# NU-SYNTHS_MIDICV_CONN.net
KiCad netlist of a schematic drawn in Altium Designer
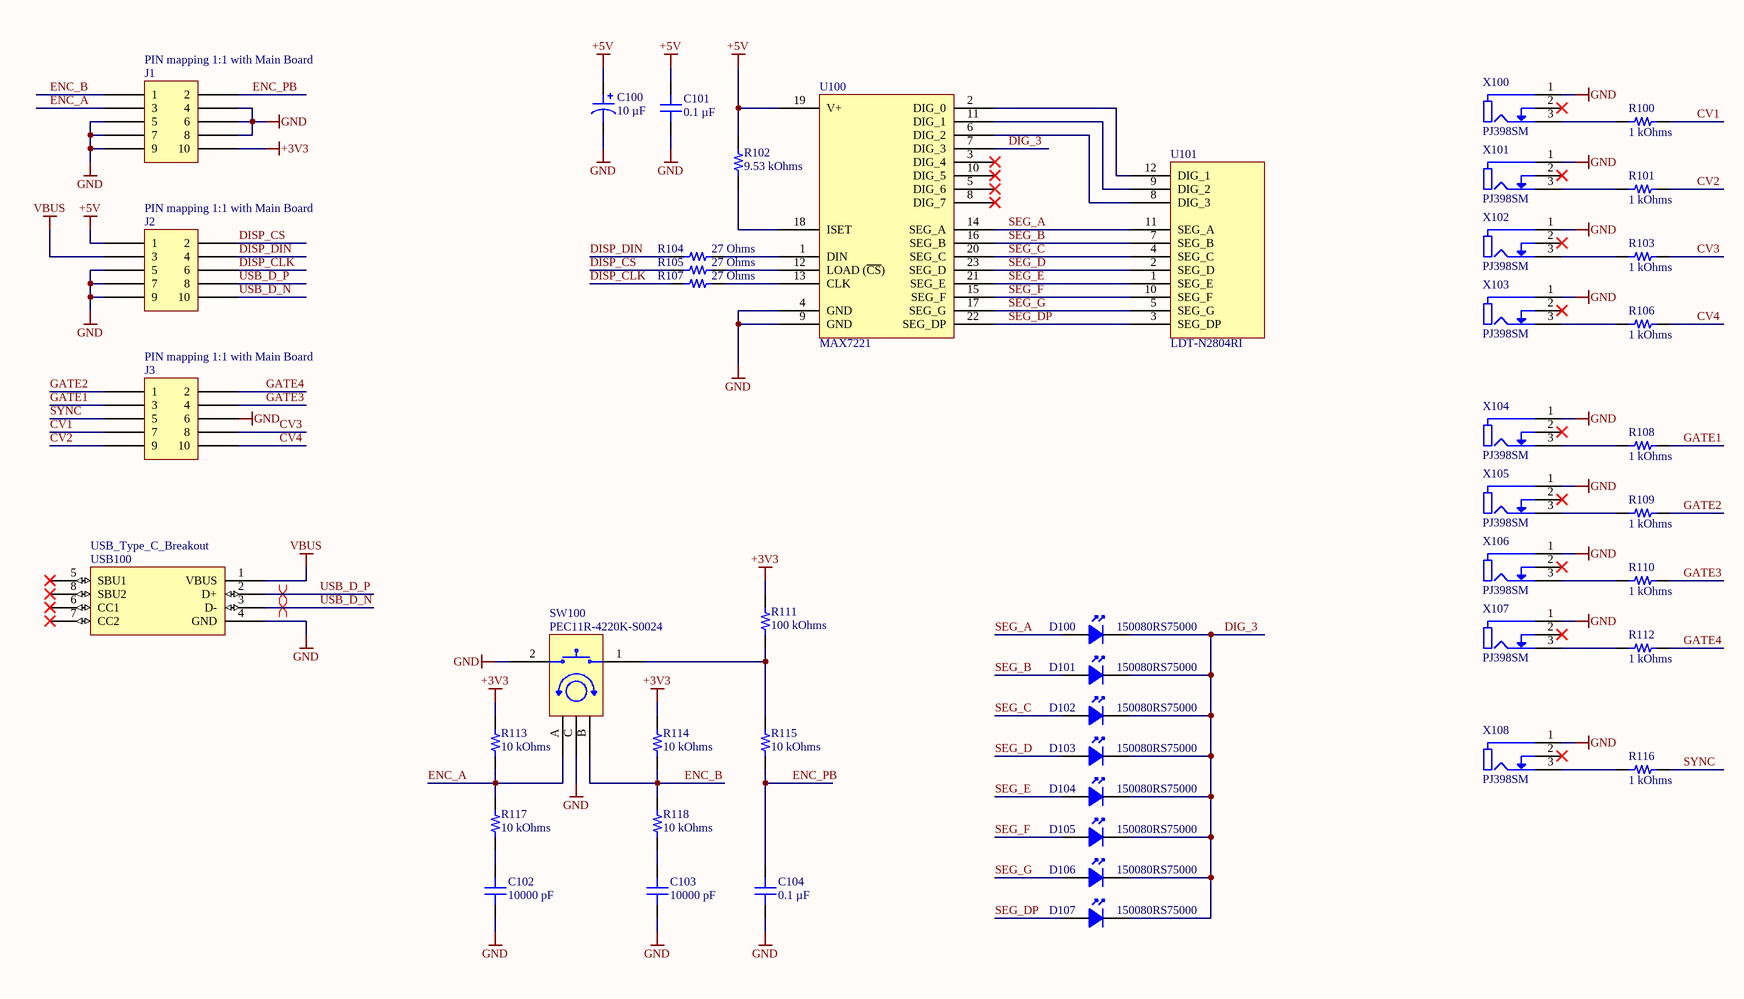
[diagram p0: NU-SYNTHS_MIDICV_CONN.SchDoc]

(export (version "E")
  (design (tool "Eeschema 10.0.6"))
  (components
    (comp (ref "C100")
      (value "10 µF")
      (footprint "CAP ALSMD 4.3MM H5.4MM")
      (description "CAP ALUM 10UF 20% 16V SMD")
      (fields (field (name "PART NUMBER") "UWX1C100MCL1GB") (field (name "MANUFACTURER") "Nichicon"))
      (libsource (lib "Celestial Altium Library") (part "Polarised Capacitor"))
    )
    (comp (ref "C101")
      (value "0.1 µF")
      (footprint "CAP 0603_1608")
      (description "CAP CER 0.1UF 25V Y5V 0603")
      (fields (field (name "PART NUMBER") "CC0603MRY5V8BB104") (field (name "MANUFACTURER") "Yageo"))
      (libsource (lib "Celestial Altium Library") (part "Capacitor"))
    )
    (comp (ref "C102")
      (value "10000 pF")
      (footprint "CAP 0603_1608")
      (description "CAP CER 10000PF 50V X7R 0603")
      (fields (field (name "PART NUMBER") "CC0603KRX7R9BB103") (field (name "MANUFACTURER") "Yageo"))
      (libsource (lib "Celestial Altium Library") (part "Capacitor"))
    )
    (comp (ref "C103")
      (value "10000 pF")
      (footprint "CAP 0603_1608")
      (description "CAP CER 10000PF 50V X7R 0603")
      (fields (field (name "PART NUMBER") "CC0603KRX7R9BB103") (field (name "MANUFACTURER") "Yageo"))
      (libsource (lib "Celestial Altium Library") (part "Capacitor"))
    )
    (comp (ref "C104")
      (value "0.1 µF")
      (footprint "CAP 0603_1608")
      (description "CAP CER 0.1UF 25V Y5V 0603")
      (fields (field (name "PART NUMBER") "CC0603MRY5V8BB104") (field (name "MANUFACTURER") "Yageo"))
      (libsource (lib "Celestial Altium Library") (part "Capacitor"))
    )
    (comp (ref "D100")
      (value "150080RS75000")
      (footprint "LED0805_PIPE")
      (description "Standard LEDs - SMD WL-SMCW SMDMono TpVw Waterclr 0805 Red")
      (libsource (lib "LabratsSynthLib") (part "150080RS75000"))
    )
    (comp (ref "D101")
      (value "150080RS75000")
      (footprint "LED0805_PIPE")
      (description "Standard LEDs - SMD WL-SMCW SMDMono TpVw Waterclr 0805 Red")
      (libsource (lib "LabratsSynthLib") (part "150080RS75000"))
    )
    (comp (ref "D102")
      (value "150080RS75000")
      (footprint "LED0805_PIPE")
      (description "Standard LEDs - SMD WL-SMCW SMDMono TpVw Waterclr 0805 Red")
      (libsource (lib "LabratsSynthLib") (part "150080RS75000"))
    )
    (comp (ref "D103")
      (value "150080RS75000")
      (footprint "LED0805_PIPE")
      (description "Standard LEDs - SMD WL-SMCW SMDMono TpVw Waterclr 0805 Red")
      (libsource (lib "LabratsSynthLib") (part "150080RS75000"))
    )
    (comp (ref "D104")
      (value "150080RS75000")
      (footprint "LED0805_PIPE")
      (description "Standard LEDs - SMD WL-SMCW SMDMono TpVw Waterclr 0805 Red")
      (libsource (lib "LabratsSynthLib") (part "150080RS75000"))
    )
    (comp (ref "D105")
      (value "150080RS75000")
      (footprint "LED0805_PIPE")
      (description "Standard LEDs - SMD WL-SMCW SMDMono TpVw Waterclr 0805 Red")
      (libsource (lib "LabratsSynthLib") (part "150080RS75000"))
    )
    (comp (ref "D106")
      (value "150080RS75000")
      (footprint "LED0805_PIPE")
      (description "Standard LEDs - SMD WL-SMCW SMDMono TpVw Waterclr 0805 Red")
      (libsource (lib "LabratsSynthLib") (part "150080RS75000"))
    )
    (comp (ref "D107")
      (value "150080RS75000")
      (footprint "LED0805_PIPE")
      (description "Standard LEDs - SMD WL-SMCW SMDMono TpVw Waterclr 0805 Red")
      (libsource (lib "LabratsSynthLib") (part "150080RS75000"))
    )
    (comp (ref "J1")
      (value "GENERIC_HEADER_2x5")
      (footprint "HEADER_2x5_TH_MALE_MIRRORED")
      (description "Generic 2x5 header")
      (libsource (lib "LabratsSynthLib") (part "GENERIC_HEADER_2x5"))
    )
    (comp (ref "J2")
      (value "GENERIC_HEADER_2x5")
      (footprint "HEADER_2x5_TH_MALE_MIRRORED")
      (description "Generic 2x5 header")
      (libsource (lib "LabratsSynthLib") (part "GENERIC_HEADER_2x5"))
    )
    (comp (ref "J3")
      (value "GENERIC_HEADER_2x5")
      (footprint "HEADER_2x5_TH_MALE_MIRRORED")
      (description "Generic 2x5 header")
      (libsource (lib "LabratsSynthLib") (part "GENERIC_HEADER_2x5"))
    )
    (comp (ref "R100")
      (value "1 kOhms")
      (footprint "RES 0603_1608")
      (description "RES 1K OHM 1% 1/10W 0603")
      (fields (field (name "PART NUMBER") "CRCW06031K00FKEAC") (field (name "MANUFACTURER") "Vishay Dale"))
      (libsource (lib "Celestial Altium Library") (part "Resistor"))
    )
    (comp (ref "R101")
      (value "1 kOhms")
      (footprint "RES 0603_1608")
      (description "RES 1K OHM 1% 1/10W 0603")
      (fields (field (name "PART NUMBER") "CRCW06031K00FKEAC") (field (name "MANUFACTURER") "Vishay Dale"))
      (libsource (lib "Celestial Altium Library") (part "Resistor"))
    )
    (comp (ref "R102")
      (value "9.53 kOhms")
      (footprint "RES 0603_1608")
      (description "RES SMD 9.53K OHM 1% 1/10W 0603")
      (fields (field (name "PART NUMBER") "CRCW06039K53FKEA") (field (name "MANUFACTURER") "Vishay Dale"))
      (libsource (lib "Celestial Altium Library") (part "Resistor"))
    )
    (comp (ref "R103")
      (value "1 kOhms")
      (footprint "RES 0603_1608")
      (description "RES 1K OHM 1% 1/10W 0603")
      (fields (field (name "PART NUMBER") "CRCW06031K00FKEAC") (field (name "MANUFACTURER") "Vishay Dale"))
      (libsource (lib "Celestial Altium Library") (part "Resistor"))
    )
    (comp (ref "R104")
      (value "27 Ohms")
      (footprint "RES 0603_1608")
      (description "RES SMD 27 OHM 1% 1/10W 0603")
      (fields (field (name "PART NUMBER") "CRCW060327R0FKEA") (field (name "MANUFACTURER") "Vishay Dale"))
      (libsource (lib "Celestial Altium Library") (part "Resistor"))
    )
    (comp (ref "R105")
      (value "27 Ohms")
      (footprint "RES 0603_1608")
      (description "RES SMD 27 OHM 1% 1/10W 0603")
      (fields (field (name "PART NUMBER") "CRCW060327R0FKEA") (field (name "MANUFACTURER") "Vishay Dale"))
      (libsource (lib "Celestial Altium Library") (part "Resistor"))
    )
    (comp (ref "R106")
      (value "1 kOhms")
      (footprint "RES 0603_1608")
      (description "RES 1K OHM 1% 1/10W 0603")
      (fields (field (name "PART NUMBER") "CRCW06031K00FKEAC") (field (name "MANUFACTURER") "Vishay Dale"))
      (libsource (lib "Celestial Altium Library") (part "Resistor"))
    )
    (comp (ref "R107")
      (value "27 Ohms")
      (footprint "RES 0603_1608")
      (description "RES SMD 27 OHM 1% 1/10W 0603")
      (fields (field (name "PART NUMBER") "CRCW060327R0FKEA") (field (name "MANUFACTURER") "Vishay Dale"))
      (libsource (lib "Celestial Altium Library") (part "Resistor"))
    )
    (comp (ref "R108")
      (value "1 kOhms")
      (footprint "RES 0603_1608")
      (description "RES 1K OHM 1% 1/10W 0603")
      (fields (field (name "PART NUMBER") "CRCW06031K00FKEAC") (field (name "MANUFACTURER") "Vishay Dale"))
      (libsource (lib "Celestial Altium Library") (part "Resistor"))
    )
    (comp (ref "R109")
      (value "1 kOhms")
      (footprint "RES 0603_1608")
      (description "RES 1K OHM 1% 1/10W 0603")
      (fields (field (name "PART NUMBER") "CRCW06031K00FKEAC") (field (name "MANUFACTURER") "Vishay Dale"))
      (libsource (lib "Celestial Altium Library") (part "Resistor"))
    )
    (comp (ref "R110")
      (value "1 kOhms")
      (footprint "RES 0603_1608")
      (description "RES 1K OHM 1% 1/10W 0603")
      (fields (field (name "PART NUMBER") "CRCW06031K00FKEAC") (field (name "MANUFACTURER") "Vishay Dale"))
      (libsource (lib "Celestial Altium Library") (part "Resistor"))
    )
    (comp (ref "R111")
      (value "100 kOhms")
      (footprint "RES 0603_1608")
      (description "RES 100K OHM 1% 1/10W 0603")
      (fields (field (name "PART NUMBER") "CRCW0603100KFKEAC") (field (name "MANUFACTURER") "Vishay Dale"))
      (libsource (lib "Celestial Altium Library") (part "Resistor"))
    )
    (comp (ref "R112")
      (value "1 kOhms")
      (footprint "RES 0603_1608")
      (description "RES 1K OHM 1% 1/10W 0603")
      (fields (field (name "PART NUMBER") "CRCW06031K00FKEAC") (field (name "MANUFACTURER") "Vishay Dale"))
      (libsource (lib "Celestial Altium Library") (part "Resistor"))
    )
    (comp (ref "R113")
      (value "10 kOhms")
      (footprint "RES 0603_1608")
      (description "RES SMD 10K OHM 1% 1/10W 0603")
      (fields (field (name "PART NUMBER") "CRCW060310K0FKTA") (field (name "MANUFACTURER") "Vishay Dale"))
      (libsource (lib "Celestial Altium Library") (part "Resistor"))
    )
    (comp (ref "R114")
      (value "10 kOhms")
      (footprint "RES 0603_1608")
      (description "RES SMD 10K OHM 1% 1/10W 0603")
      (fields (field (name "PART NUMBER") "CRCW060310K0FKTA") (field (name "MANUFACTURER") "Vishay Dale"))
      (libsource (lib "Celestial Altium Library") (part "Resistor"))
    )
    (comp (ref "R115")
      (value "10 kOhms")
      (footprint "RES 0603_1608")
      (description "RES SMD 10K OHM 1% 1/10W 0603")
      (fields (field (name "PART NUMBER") "CRCW060310K0FKTA") (field (name "MANUFACTURER") "Vishay Dale"))
      (libsource (lib "Celestial Altium Library") (part "Resistor"))
    )
    (comp (ref "R116")
      (value "1 kOhms")
      (footprint "RES 0603_1608")
      (description "RES 1K OHM 1% 1/10W 0603")
      (fields (field (name "PART NUMBER") "CRCW06031K00FKEAC") (field (name "MANUFACTURER") "Vishay Dale"))
      (libsource (lib "Celestial Altium Library") (part "Resistor"))
    )
    (comp (ref "R117")
      (value "10 kOhms")
      (footprint "RES 0603_1608")
      (description "RES SMD 10K OHM 1% 1/10W 0603")
      (fields (field (name "PART NUMBER") "CRCW060310K0FKTA") (field (name "MANUFACTURER") "Vishay Dale"))
      (libsource (lib "Celestial Altium Library") (part "Resistor"))
    )
    (comp (ref "R118")
      (value "10 kOhms")
      (footprint "RES 0603_1608")
      (description "RES SMD 10K OHM 1% 1/10W 0603")
      (fields (field (name "PART NUMBER") "CRCW060310K0FKTA") (field (name "MANUFACTURER") "Vishay Dale"))
      (libsource (lib "Celestial Altium Library") (part "Resistor"))
    )
    (comp (ref "SW100")
      (value "PEC11R-4220K-S0024")
      (footprint "PEC11R-4220K-S0024")
      (description "Encoders 20mm SHAFT w/SWITCH")
      (libsource (lib "LabratsSynthLib") (part "PEC11R-4220K-S0024"))
    )
    (comp (ref "U100")
      (value "MAX7221")
      (footprint "SOIC127P1032X265-24N")
      (description "LED Driver, 4V to 5.5V input, 8 Outputs, 10 MHz Switch. Frequency, 4.5V/320 mA out, SOIC-24")
      (libsource (lib "LabratsSynthLib") (part "MAX7221"))
    )
    (comp (ref "U101")
      (value "LDT-N2804RI")
      (footprint "LDT-N2804RI")
      (description "Common Cathode, 3 Digit 7 Segment Display, 0.28''")
      (libsource (lib "LabratsSynthLib") (part "LDT-N2804RI"))
    )
    (comp (ref "USB100")
      (value "USB_Type_C_Breakout")
      (footprint "USBC_BREAKOUT_NO_TH")
      (description "USB type C Breakout Board")
      (libsource (lib "LabratsSynthLib") (part "USBC_Breakout"))
    )
    (comp (ref "X100")
      (value "PJ398SM")
      (footprint "PJ398SM")
      (description "Vertical mount 3.5mm switching mono jack.")
      (libsource (lib "LabratsSynthLib") (part "PJ398SM"))
    )
    (comp (ref "X101")
      (value "PJ398SM")
      (footprint "PJ398SM")
      (description "Vertical mount 3.5mm switching mono jack.")
      (libsource (lib "LabratsSynthLib") (part "PJ398SM"))
    )
    (comp (ref "X102")
      (value "PJ398SM")
      (footprint "PJ398SM")
      (description "Vertical mount 3.5mm switching mono jack.")
      (libsource (lib "LabratsSynthLib") (part "PJ398SM"))
    )
    (comp (ref "X103")
      (value "PJ398SM")
      (footprint "PJ398SM")
      (description "Vertical mount 3.5mm switching mono jack.")
      (libsource (lib "LabratsSynthLib") (part "PJ398SM"))
    )
    (comp (ref "X104")
      (value "PJ398SM")
      (footprint "PJ398SM")
      (description "Vertical mount 3.5mm switching mono jack.")
      (libsource (lib "LabratsSynthLib") (part "PJ398SM"))
    )
    (comp (ref "X105")
      (value "PJ398SM")
      (footprint "PJ398SM")
      (description "Vertical mount 3.5mm switching mono jack.")
      (libsource (lib "LabratsSynthLib") (part "PJ398SM"))
    )
    (comp (ref "X106")
      (value "PJ398SM")
      (footprint "PJ398SM")
      (description "Vertical mount 3.5mm switching mono jack.")
      (libsource (lib "LabratsSynthLib") (part "PJ398SM"))
    )
    (comp (ref "X107")
      (value "PJ398SM")
      (footprint "PJ398SM")
      (description "Vertical mount 3.5mm switching mono jack.")
      (libsource (lib "LabratsSynthLib") (part "PJ398SM"))
    )
    (comp (ref "X108")
      (value "PJ398SM")
      (footprint "PJ398SM")
      (description "Vertical mount 3.5mm switching mono jack.")
      (libsource (lib "LabratsSynthLib") (part "PJ398SM"))
    )
  )
  (nets
    (net (code "1") (name "+3V3") (class "Default")
      (node (ref "J1") (pin "10") (pinfunction "10_10") (pintype "passive"))
      (node (ref "R111") (pin "2") (pinfunction "2_2") (pintype "passive"))
      (node (ref "R113") (pin "2") (pinfunction "2_2") (pintype "passive"))
      (node (ref "R114") (pin "2") (pinfunction "2_2") (pintype "passive"))
    )
    (net (code "2") (name "+5V") (class "Default")
      (node (ref "C100") (pin "1") (pinfunction "1_1") (pintype "passive"))
      (node (ref "C101") (pin "2") (pinfunction "2_2") (pintype "passive"))
      (node (ref "J2") (pin "1") (pinfunction "1_1") (pintype "passive"))
      (node (ref "R102") (pin "2") (pinfunction "2_2") (pintype "passive"))
      (node (ref "U100") (pin "19") (pinfunction "V+_19") (pintype "passive"))
    )
    (net (code "3") (name "/CV1") (class "Default")
      (node (ref "J3") (pin "7") (pinfunction "7_7") (pintype "passive"))
      (node (ref "R100") (pin "2") (pinfunction "2_2") (pintype "passive"))
    )
    (net (code "4") (name "/CV2") (class "Default")
      (node (ref "J3") (pin "9") (pinfunction "9_9") (pintype "passive"))
      (node (ref "R101") (pin "2") (pinfunction "2_2") (pintype "passive"))
    )
    (net (code "5") (name "/CV3") (class "Default")
      (node (ref "J3") (pin "8") (pinfunction "8_8") (pintype "passive"))
      (node (ref "R103") (pin "2") (pinfunction "2_2") (pintype "passive"))
    )
    (net (code "6") (name "/CV4") (class "Default")
      (node (ref "J3") (pin "10") (pinfunction "10_10") (pintype "passive"))
      (node (ref "R106") (pin "2") (pinfunction "2_2") (pintype "passive"))
    )
    (net (code "7") (name "/DIG_3") (class "Default")
      (node (ref "D100") (pin "1") (pinfunction "K_1") (pintype "passive"))
      (node (ref "D101") (pin "1") (pinfunction "K_1") (pintype "passive"))
      (node (ref "D102") (pin "1") (pinfunction "K_1") (pintype "passive"))
      (node (ref "D103") (pin "1") (pinfunction "K_1") (pintype "passive"))
      (node (ref "D104") (pin "1") (pinfunction "K_1") (pintype "passive"))
      (node (ref "D105") (pin "1") (pinfunction "K_1") (pintype "passive"))
      (node (ref "D106") (pin "1") (pinfunction "K_1") (pintype "passive"))
      (node (ref "D107") (pin "1") (pinfunction "K_1") (pintype "passive"))
      (node (ref "U100") (pin "7") (pinfunction "DIG_3_7") (pintype "passive"))
    )
    (net (code "8") (name "/DISP_CLK") (class "Default")
      (node (ref "J2") (pin "6") (pinfunction "6_6") (pintype "passive"))
      (node (ref "R107") (pin "1") (pinfunction "1_1") (pintype "passive"))
    )
    (net (code "9") (name "/DISP_CS") (class "Default")
      (node (ref "J2") (pin "2") (pinfunction "2_2") (pintype "passive"))
      (node (ref "R105") (pin "1") (pinfunction "1_1") (pintype "passive"))
    )
    (net (code "10") (name "/DISP_DIN") (class "Default")
      (node (ref "J2") (pin "4") (pinfunction "4_4") (pintype "passive"))
      (node (ref "R104") (pin "1") (pinfunction "1_1") (pintype "passive"))
    )
    (net (code "11") (name "/ENC_A") (class "Default")
      (node (ref "J1") (pin "3") (pinfunction "3_3") (pintype "passive"))
      (node (ref "R113") (pin "1") (pinfunction "1_1") (pintype "passive"))
      (node (ref "R117") (pin "2") (pinfunction "2_2") (pintype "passive"))
      (node (ref "SW100") (pin "A") (pinfunction "A_A") (pintype "passive"))
    )
    (net (code "12") (name "/ENC_B") (class "Default")
      (node (ref "J1") (pin "1") (pinfunction "1_1") (pintype "passive"))
      (node (ref "R114") (pin "1") (pinfunction "1_1") (pintype "passive"))
      (node (ref "R118") (pin "2") (pinfunction "2_2") (pintype "passive"))
      (node (ref "SW100") (pin "B") (pinfunction "B_B") (pintype "passive"))
    )
    (net (code "13") (name "/ENC_PB") (class "Default")
      (node (ref "C104") (pin "2") (pinfunction "2_2") (pintype "passive"))
      (node (ref "J1") (pin "2") (pinfunction "2_2") (pintype "passive"))
      (node (ref "R115") (pin "1") (pinfunction "1_1") (pintype "passive"))
    )
    (net (code "14") (name "/GATE1") (class "Default")
      (node (ref "J3") (pin "3") (pinfunction "3_3") (pintype "passive"))
      (node (ref "R108") (pin "2") (pinfunction "2_2") (pintype "passive"))
    )
    (net (code "15") (name "/GATE2") (class "Default")
      (node (ref "J3") (pin "1") (pinfunction "1_1") (pintype "passive"))
      (node (ref "R109") (pin "2") (pinfunction "2_2") (pintype "passive"))
    )
    (net (code "16") (name "/GATE3") (class "Default")
      (node (ref "J3") (pin "4") (pinfunction "4_4") (pintype "passive"))
      (node (ref "R110") (pin "2") (pinfunction "2_2") (pintype "passive"))
    )
    (net (code "17") (name "/GATE4") (class "Default")
      (node (ref "J3") (pin "2") (pinfunction "2_2") (pintype "passive"))
      (node (ref "R112") (pin "2") (pinfunction "2_2") (pintype "passive"))
    )
    (net (code "18") (name "/SEG_A") (class "Default")
      (node (ref "D100") (pin "2") (pinfunction "A_2") (pintype "passive"))
      (node (ref "U100") (pin "14") (pinfunction "SEG_A_14") (pintype "passive"))
      (node (ref "U101") (pin "11") (pinfunction "SEG_A_11") (pintype "passive"))
    )
    (net (code "19") (name "/SEG_B") (class "Default")
      (node (ref "D101") (pin "2") (pinfunction "A_2") (pintype "passive"))
      (node (ref "U100") (pin "16") (pinfunction "SEG_B_16") (pintype "passive"))
      (node (ref "U101") (pin "7") (pinfunction "SEG_B_7") (pintype "passive"))
    )
    (net (code "20") (name "/SEG_C") (class "Default")
      (node (ref "D102") (pin "2") (pinfunction "A_2") (pintype "passive"))
      (node (ref "U100") (pin "20") (pinfunction "SEG_C_20") (pintype "passive"))
      (node (ref "U101") (pin "4") (pinfunction "SEG_C_4") (pintype "passive"))
    )
    (net (code "21") (name "/SEG_D") (class "Default")
      (node (ref "D103") (pin "2") (pinfunction "A_2") (pintype "passive"))
      (node (ref "U100") (pin "23") (pinfunction "SEG_D_23") (pintype "passive"))
      (node (ref "U101") (pin "2") (pinfunction "SEG_D_2") (pintype "passive"))
    )
    (net (code "22") (name "/SEG_DP") (class "Default")
      (node (ref "D107") (pin "2") (pinfunction "A_2") (pintype "passive"))
      (node (ref "U100") (pin "22") (pinfunction "SEG_DP_22") (pintype "passive"))
      (node (ref "U101") (pin "3") (pinfunction "SEG_DP_3") (pintype "passive"))
    )
    (net (code "23") (name "/SEG_E") (class "Default")
      (node (ref "D104") (pin "2") (pinfunction "A_2") (pintype "passive"))
      (node (ref "U100") (pin "21") (pinfunction "SEG_E_21") (pintype "passive"))
      (node (ref "U101") (pin "1") (pinfunction "SEG_E_1") (pintype "passive"))
    )
    (net (code "24") (name "/SEG_F") (class "Default")
      (node (ref "D105") (pin "2") (pinfunction "A_2") (pintype "passive"))
      (node (ref "U100") (pin "15") (pinfunction "SEG_F_15") (pintype "passive"))
      (node (ref "U101") (pin "10") (pinfunction "SEG_F_10") (pintype "passive"))
    )
    (net (code "25") (name "/SEG_G") (class "Default")
      (node (ref "D106") (pin "2") (pinfunction "A_2") (pintype "passive"))
      (node (ref "U100") (pin "17") (pinfunction "SEG_G_17") (pintype "passive"))
      (node (ref "U101") (pin "5") (pinfunction "SEG_G_5") (pintype "passive"))
    )
    (net (code "26") (name "/SYNC") (class "Default")
      (node (ref "J3") (pin "5") (pinfunction "5_5") (pintype "passive"))
      (node (ref "R116") (pin "2") (pinfunction "2_2") (pintype "passive"))
    )
    (net (code "27") (name "/USB_D_N") (class "Default")
      (node (ref "J2") (pin "10") (pinfunction "10_10") (pintype "passive"))
      (node (ref "USB100") (pin "3") (pinfunction "D-_3") (pintype "bidirectional"))
    )
    (net (code "28") (name "/USB_D_P") (class "Default")
      (node (ref "J2") (pin "8") (pinfunction "8_8") (pintype "passive"))
      (node (ref "USB100") (pin "2") (pinfunction "D+_2") (pintype "bidirectional"))
    )
    (net (code "29") (name "GND") (class "Default")
      (node (ref "C100") (pin "2") (pinfunction "2_2") (pintype "passive"))
      (node (ref "C101") (pin "1") (pinfunction "1_1") (pintype "passive"))
      (node (ref "C102") (pin "1") (pinfunction "1_1") (pintype "passive"))
      (node (ref "C103") (pin "1") (pinfunction "1_1") (pintype "passive"))
      (node (ref "C104") (pin "1") (pinfunction "1_1") (pintype "passive"))
      (node (ref "J1") (pin "4") (pinfunction "4_4") (pintype "passive"))
      (node (ref "J1") (pin "5") (pinfunction "5_5") (pintype "passive"))
      (node (ref "J1") (pin "6") (pinfunction "6_6") (pintype "passive"))
      (node (ref "J1") (pin "7") (pinfunction "7_7") (pintype "passive"))
      (node (ref "J1") (pin "8") (pinfunction "8_8") (pintype "passive"))
      (node (ref "J1") (pin "9") (pinfunction "9_9") (pintype "passive"))
      (node (ref "J2") (pin "5") (pinfunction "5_5") (pintype "passive"))
      (node (ref "J2") (pin "7") (pinfunction "7_7") (pintype "passive"))
      (node (ref "J2") (pin "9") (pinfunction "9_9") (pintype "passive"))
      (node (ref "J3") (pin "6") (pinfunction "6_6") (pintype "passive"))
      (node (ref "SW100") (pin "2") (pinfunction "2_2") (pintype "passive"))
      (node (ref "SW100") (pin "C") (pinfunction "C_C") (pintype "passive"))
      (node (ref "U100") (pin "4") (pinfunction "GND_4") (pintype "power_in"))
      (node (ref "U100") (pin "9") (pinfunction "GND_9") (pintype "power_in"))
      (node (ref "USB100") (pin "4") (pinfunction "GND_4") (pintype "power_in"))
      (node (ref "X100") (pin "1") (pinfunction "SLEEVE_1") (pintype "passive"))
      (node (ref "X101") (pin "1") (pinfunction "SLEEVE_1") (pintype "passive"))
      (node (ref "X102") (pin "1") (pinfunction "SLEEVE_1") (pintype "passive"))
      (node (ref "X103") (pin "1") (pinfunction "SLEEVE_1") (pintype "passive"))
      (node (ref "X104") (pin "1") (pinfunction "SLEEVE_1") (pintype "passive"))
      (node (ref "X105") (pin "1") (pinfunction "SLEEVE_1") (pintype "passive"))
      (node (ref "X106") (pin "1") (pinfunction "SLEEVE_1") (pintype "passive"))
      (node (ref "X107") (pin "1") (pinfunction "SLEEVE_1") (pintype "passive"))
      (node (ref "X108") (pin "1") (pinfunction "SLEEVE_1") (pintype "passive"))
    )
    (net (code "30") (name "Net-(C102-Pad2)") (class "Default")
      (node (ref "C102") (pin "2") (pinfunction "2_2") (pintype "passive"))
      (node (ref "R117") (pin "1") (pinfunction "1_1") (pintype "passive"))
    )
    (net (code "31") (name "Net-(C103-Pad2)") (class "Default")
      (node (ref "C103") (pin "2") (pinfunction "2_2") (pintype "passive"))
      (node (ref "R118") (pin "1") (pinfunction "1_1") (pintype "passive"))
    )
    (net (code "32") (name "Net-(R111-Pad1)") (class "Default")
      (node (ref "R111") (pin "1") (pinfunction "1_1") (pintype "passive"))
      (node (ref "R115") (pin "2") (pinfunction "2_2") (pintype "passive"))
      (node (ref "SW100") (pin "1") (pinfunction "1_1") (pintype "passive"))
    )
    (net (code "33") (name "Net-(U100-CLK)") (class "Default")
      (node (ref "R107") (pin "2") (pinfunction "2_2") (pintype "passive"))
      (node (ref "U100") (pin "13") (pinfunction "CLK_13") (pintype "power_in"))
    )
    (net (code "34") (name "Net-(U100-DIG_0)") (class "Default")
      (node (ref "U100") (pin "2") (pinfunction "DIG_0_2") (pintype "passive"))
      (node (ref "U101") (pin "12") (pinfunction "DIG_1_12") (pintype "power_in"))
    )
    (net (code "35") (name "Net-(U100-DIG_1)") (class "Default")
      (node (ref "U100") (pin "11") (pinfunction "DIG_1_11") (pintype "passive"))
      (node (ref "U101") (pin "9") (pinfunction "DIG_2_9") (pintype "power_in"))
    )
    (net (code "36") (name "Net-(U100-DIG_2)") (class "Default")
      (node (ref "U100") (pin "6") (pinfunction "DIG_2_6") (pintype "passive"))
      (node (ref "U101") (pin "8") (pinfunction "DIG_3_8") (pintype "power_in"))
    )
    (net (code "37") (name "Net-(U100-DIN)") (class "Default")
      (node (ref "R104") (pin "2") (pinfunction "2_2") (pintype "passive"))
      (node (ref "U100") (pin "1") (pinfunction "DIN_1") (pintype "power_in"))
    )
    (net (code "38") (name "Net-(U100-ISET)") (class "Default")
      (node (ref "R102") (pin "1") (pinfunction "1_1") (pintype "passive"))
      (node (ref "U100") (pin "18") (pinfunction "ISET_18") (pintype "power_in"))
    )
    (net (code "39") (name "Net-(U100-LOAD_(~{CS}))") (class "Default")
      (node (ref "R105") (pin "2") (pinfunction "2_2") (pintype "passive"))
      (node (ref "U100") (pin "12") (pinfunction "LOAD_(~{CS})_12") (pintype "power_in"))
    )
    (net (code "40") (name "Net-(X100-RING)") (class "Default")
      (node (ref "R100") (pin "1") (pinfunction "1_1") (pintype "passive"))
      (node (ref "X100") (pin "3") (pinfunction "RING_3") (pintype "passive"))
    )
    (net (code "41") (name "Net-(X101-RING)") (class "Default")
      (node (ref "R101") (pin "1") (pinfunction "1_1") (pintype "passive"))
      (node (ref "X101") (pin "3") (pinfunction "RING_3") (pintype "passive"))
    )
    (net (code "42") (name "Net-(X102-RING)") (class "Default")
      (node (ref "R103") (pin "1") (pinfunction "1_1") (pintype "passive"))
      (node (ref "X102") (pin "3") (pinfunction "RING_3") (pintype "passive"))
    )
    (net (code "43") (name "Net-(X103-RING)") (class "Default")
      (node (ref "R106") (pin "1") (pinfunction "1_1") (pintype "passive"))
      (node (ref "X103") (pin "3") (pinfunction "RING_3") (pintype "passive"))
    )
    (net (code "44") (name "Net-(X104-RING)") (class "Default")
      (node (ref "R108") (pin "1") (pinfunction "1_1") (pintype "passive"))
      (node (ref "X104") (pin "3") (pinfunction "RING_3") (pintype "passive"))
    )
    (net (code "45") (name "Net-(X105-RING)") (class "Default")
      (node (ref "R109") (pin "1") (pinfunction "1_1") (pintype "passive"))
      (node (ref "X105") (pin "3") (pinfunction "RING_3") (pintype "passive"))
    )
    (net (code "46") (name "Net-(X106-RING)") (class "Default")
      (node (ref "R110") (pin "1") (pinfunction "1_1") (pintype "passive"))
      (node (ref "X106") (pin "3") (pinfunction "RING_3") (pintype "passive"))
    )
    (net (code "47") (name "Net-(X107-RING)") (class "Default")
      (node (ref "R112") (pin "1") (pinfunction "1_1") (pintype "passive"))
      (node (ref "X107") (pin "3") (pinfunction "RING_3") (pintype "passive"))
    )
    (net (code "48") (name "Net-(X108-RING)") (class "Default")
      (node (ref "R116") (pin "1") (pinfunction "1_1") (pintype "passive"))
      (node (ref "X108") (pin "3") (pinfunction "RING_3") (pintype "passive"))
    )
    (net (code "49") (name "VBUS") (class "Default")
      (node (ref "J2") (pin "3") (pinfunction "3_3") (pintype "passive"))
      (node (ref "USB100") (pin "1") (pinfunction "VBUS_1") (pintype "power_in"))
    )
    (net (code "50") (name "unconnected-(U100-DIG_4-Pad3)") (class "Default")
      (node (ref "U100") (pin "3") (pinfunction "DIG_4_3") (pintype "passive+no_connect"))
    )
    (net (code "51") (name "unconnected-(U100-DIG_5-Pad10)") (class "Default")
      (node (ref "U100") (pin "10") (pinfunction "DIG_5_10") (pintype "passive+no_connect"))
    )
    (net (code "52") (name "unconnected-(U100-DIG_6-Pad5)") (class "Default")
      (node (ref "U100") (pin "5") (pinfunction "DIG_6_5") (pintype "passive+no_connect"))
    )
    (net (code "53") (name "unconnected-(U100-DIG_7-Pad8)") (class "Default")
      (node (ref "U100") (pin "8") (pinfunction "DIG_7_8") (pintype "passive+no_connect"))
    )
    (net (code "54") (name "unconnected-(USB100-CC1-Pad6)") (class "Default")
      (node (ref "USB100") (pin "6") (pinfunction "CC1_6") (pintype "bidirectional+no_connect"))
    )
    (net (code "55") (name "unconnected-(USB100-CC2-Pad7)") (class "Default")
      (node (ref "USB100") (pin "7") (pinfunction "CC2_7") (pintype "bidirectional+no_connect"))
    )
    (net (code "56") (name "unconnected-(USB100-SBU1-Pad5)") (class "Default")
      (node (ref "USB100") (pin "5") (pinfunction "SBU1_5") (pintype "bidirectional+no_connect"))
    )
    (net (code "57") (name "unconnected-(USB100-SBU2-Pad8)") (class "Default")
      (node (ref "USB100") (pin "8") (pinfunction "SBU2_8") (pintype "bidirectional+no_connect"))
    )
    (net (code "58") (name "unconnected-(X100-TIP-Pad2)") (class "Default")
      (node (ref "X100") (pin "2") (pinfunction "TIP_2") (pintype "passive+no_connect"))
    )
    (net (code "59") (name "unconnected-(X101-TIP-Pad2)") (class "Default")
      (node (ref "X101") (pin "2") (pinfunction "TIP_2") (pintype "passive+no_connect"))
    )
    (net (code "60") (name "unconnected-(X102-TIP-Pad2)") (class "Default")
      (node (ref "X102") (pin "2") (pinfunction "TIP_2") (pintype "passive+no_connect"))
    )
    (net (code "61") (name "unconnected-(X103-TIP-Pad2)") (class "Default")
      (node (ref "X103") (pin "2") (pinfunction "TIP_2") (pintype "passive+no_connect"))
    )
    (net (code "62") (name "unconnected-(X104-TIP-Pad2)") (class "Default")
      (node (ref "X104") (pin "2") (pinfunction "TIP_2") (pintype "passive+no_connect"))
    )
    (net (code "63") (name "unconnected-(X105-TIP-Pad2)") (class "Default")
      (node (ref "X105") (pin "2") (pinfunction "TIP_2") (pintype "passive+no_connect"))
    )
    (net (code "64") (name "unconnected-(X106-TIP-Pad2)") (class "Default")
      (node (ref "X106") (pin "2") (pinfunction "TIP_2") (pintype "passive+no_connect"))
    )
    (net (code "65") (name "unconnected-(X107-TIP-Pad2)") (class "Default")
      (node (ref "X107") (pin "2") (pinfunction "TIP_2") (pintype "passive+no_connect"))
    )
    (net (code "66") (name "unconnected-(X108-TIP-Pad2)") (class "Default")
      (node (ref "X108") (pin "2") (pinfunction "TIP_2") (pintype "passive+no_connect"))
    )
  )
)
